# Digital_Signals.net
KiCad netlist of a schematic drawn in Altium Designer
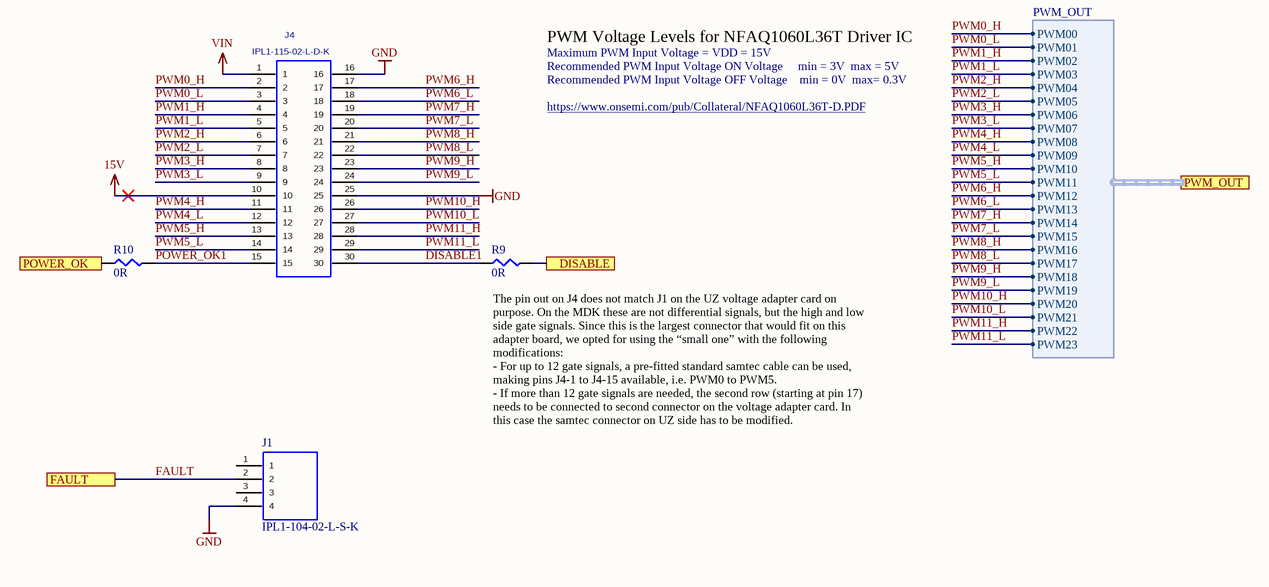
[diagram p0: Digital_Signals.SchDoc]

(export (version "E")
  (design (tool "Eeschema 10.0.6"))
  (components
    (comp (ref "J1")
      (value "IPL1-104-02-L-S-K")
      (footprint "IPL1-104-02-L-S-K")
      (libsource (lib "ultrazohm_digital_voltage_3U_1vxx") (part "IPL1-104-02-L-S-K"))
    )
    (comp (ref "J4")
      (value "IPL1-115-02-L-D-K")
      (footprint "IPL1-115-02-L-D-K")
      (description "Terminal Assembly, Double Row, Right Angle, Thru-Hole, 0.100\" x 0.100\" Pitch, 30 Pins.")
      (fields
        (field (name "MF") "SAMTEC")
        (field (name "MPN") "IPL1-115-01-L-D-RA-K")
        (field (name "CREATED") "2019-12-17_Wendy_Xin")
      )
      (libsource (lib "connectors") (part "IPL1-115-01-XX-D-RA"))
    )
    (comp (ref "R9")
      (value "0R")
      (footprint "RESC0603")
      (description "RES SMD")
      (fields (field (name "PART NUMBER") "Generic 1% tol.") (field (name "PUBLISHER") "Generic"))
      (libsource (lib "Res_SMD") (part "RES_SMD"))
    )
    (comp (ref "R10")
      (value "0R")
      (footprint "RESC0603")
      (description "RES SMD")
      (fields (field (name "PART NUMBER") "Generic 1% tol.") (field (name "PUBLISHER") "Generic"))
      (libsource (lib "Res_SMD") (part "RES_SMD"))
    )
  )
  (nets
    (net (code "2") (name "/DISABLE") (class "Default")
      (node (ref "R9") (pin "2") (pinfunction "2_2") (pintype "passive"))
    )
    (net (code "3") (name "/DISABLE1") (class "Default")
      (node (ref "J4") (pin "30") (pinfunction "30_30") (pintype "passive"))
      (node (ref "R9") (pin "1") (pinfunction "1_1") (pintype "passive"))
    )
    (net (code "4") (name "/FAULT") (class "Default")
      (node (ref "J1") (pin "2") (pinfunction "2_2") (pintype "passive"))
    )
    (net (code "5") (name "/POWER_OK") (class "Default")
      (node (ref "R10") (pin "1") (pinfunction "1_1") (pintype "passive"))
    )
    (net (code "6") (name "/POWER_OK1") (class "Default")
      (node (ref "J4") (pin "15") (pinfunction "15_15") (pintype "passive"))
      (node (ref "R10") (pin "2") (pinfunction "2_2") (pintype "passive"))
    )
    (net (code "7") (name "/PWM0_H") (class "Default")
      (node (ref "J4") (pin "2") (pinfunction "2_2") (pintype "passive"))
    )
    (net (code "8") (name "/PWM0_L") (class "Default")
      (node (ref "J4") (pin "3") (pinfunction "3_3") (pintype "passive"))
    )
    (net (code "9") (name "/PWM1_H") (class "Default")
      (node (ref "J4") (pin "4") (pinfunction "4_4") (pintype "passive"))
    )
    (net (code "10") (name "/PWM1_L") (class "Default")
      (node (ref "J4") (pin "5") (pinfunction "5_5") (pintype "passive"))
    )
    (net (code "11") (name "/PWM2_H") (class "Default")
      (node (ref "J4") (pin "6") (pinfunction "6_6") (pintype "passive"))
    )
    (net (code "12") (name "/PWM2_L") (class "Default")
      (node (ref "J4") (pin "7") (pinfunction "7_7") (pintype "passive"))
    )
    (net (code "13") (name "/PWM3_H") (class "Default")
      (node (ref "J4") (pin "8") (pinfunction "8_8") (pintype "passive"))
    )
    (net (code "14") (name "/PWM3_L") (class "Default")
      (node (ref "J4") (pin "9") (pinfunction "9_9") (pintype "passive"))
    )
    (net (code "15") (name "/PWM4_H") (class "Default")
      (node (ref "J4") (pin "11") (pinfunction "11_11") (pintype "passive"))
    )
    (net (code "16") (name "/PWM4_L") (class "Default")
      (node (ref "J4") (pin "12") (pinfunction "12_12") (pintype "passive"))
    )
    (net (code "17") (name "/PWM5_H") (class "Default")
      (node (ref "J4") (pin "13") (pinfunction "13_13") (pintype "passive"))
    )
    (net (code "18") (name "/PWM5_L") (class "Default")
      (node (ref "J4") (pin "14") (pinfunction "14_14") (pintype "passive"))
    )
    (net (code "19") (name "/PWM6_H") (class "Default")
      (node (ref "J4") (pin "17") (pinfunction "17_17") (pintype "passive"))
    )
    (net (code "20") (name "/PWM6_L") (class "Default")
      (node (ref "J4") (pin "18") (pinfunction "18_18") (pintype "passive"))
    )
    (net (code "21") (name "/PWM7_H") (class "Default")
      (node (ref "J4") (pin "19") (pinfunction "19_19") (pintype "passive"))
    )
    (net (code "22") (name "/PWM7_L") (class "Default")
      (node (ref "J4") (pin "20") (pinfunction "20_20") (pintype "passive"))
    )
    (net (code "23") (name "/PWM8_H") (class "Default")
      (node (ref "J4") (pin "21") (pinfunction "21_21") (pintype "passive"))
    )
    (net (code "24") (name "/PWM8_L") (class "Default")
      (node (ref "J4") (pin "22") (pinfunction "22_22") (pintype "passive"))
    )
    (net (code "25") (name "/PWM9_H") (class "Default")
      (node (ref "J4") (pin "23") (pinfunction "23_23") (pintype "passive"))
    )
    (net (code "26") (name "/PWM9_L") (class "Default")
      (node (ref "J4") (pin "24") (pinfunction "24_24") (pintype "passive"))
    )
    (net (code "27") (name "/PWM10_H") (class "Default")
      (node (ref "J4") (pin "26") (pinfunction "26_26") (pintype "passive"))
    )
    (net (code "28") (name "/PWM10_L") (class "Default")
      (node (ref "J4") (pin "27") (pinfunction "27_27") (pintype "passive"))
    )
    (net (code "29") (name "/PWM11_H") (class "Default")
      (node (ref "J4") (pin "28") (pinfunction "28_28") (pintype "passive"))
    )
    (net (code "30") (name "/PWM11_L") (class "Default")
      (node (ref "J4") (pin "29") (pinfunction "29_29") (pintype "passive"))
    )
    (net (code "32") (name "15V") (class "Default")
      (node (ref "J4") (pin "10") (pinfunction "10_10") (pintype "passive"))
    )
    (net (code "33") (name "GND") (class "Default")
      (node (ref "J1") (pin "4") (pinfunction "4_4") (pintype "passive"))
      (node (ref "J4") (pin "16") (pinfunction "16_16") (pintype "passive"))
      (node (ref "J4") (pin "25") (pinfunction "25_25") (pintype "passive"))
    )
    (net (code "34") (name "VIN") (class "Default")
      (node (ref "J4") (pin "1") (pinfunction "1_1") (pintype "passive"))
    )
    (net (code "35") (name "unconnected-(J1-Pad1)") (class "Default")
      (node (ref "J1") (pin "1") (pinfunction "1_1") (pintype "passive"))
    )
    (net (code "36") (name "unconnected-(J1-Pad3)") (class "Default")
      (node (ref "J1") (pin "3") (pinfunction "3_3") (pintype "passive"))
    )
  )
)
